# USB2Serial_MCP2200_v1_0.net
KiCad netlist of a schematic drawn in EAGLE
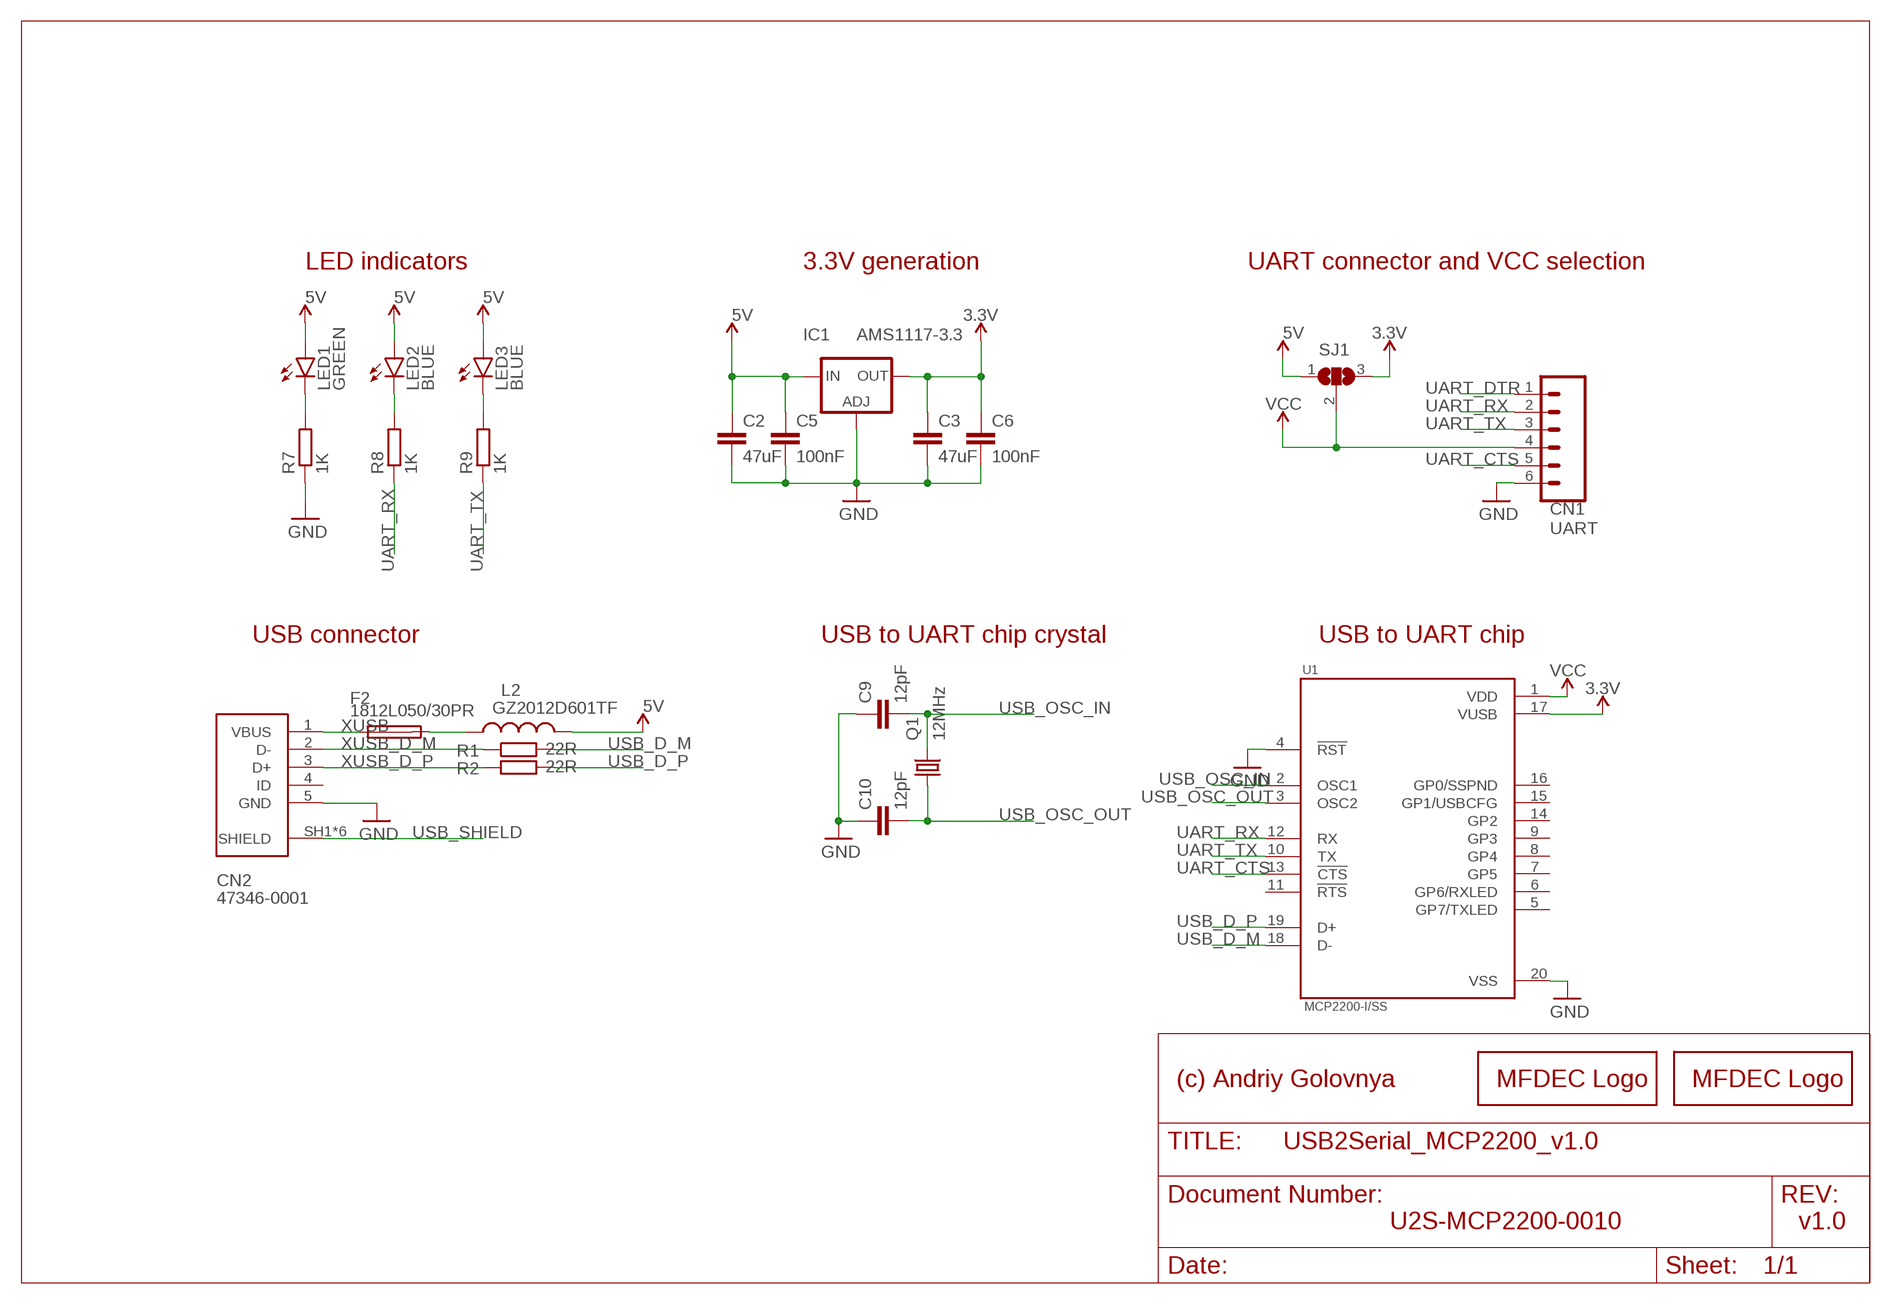
[diagram p0: schematic, sheet 1]

(export (version "E")
  (design (tool "Eeschema 10.0.6"))
  (components
    (comp (ref "C2")
      (value "47uF")
      (footprint "eagle-import:C0805")
      (libsource (lib "eagle-import") (part "C-EUC0805"))
    )
    (comp (ref "C3")
      (value "47uF")
      (footprint "eagle-import:C0805")
      (libsource (lib "eagle-import") (part "C-EUC0805"))
    )
    (comp (ref "C5")
      (value "100nF")
      (footprint "eagle-import:C0402")
      (libsource (lib "eagle-import") (part "C-EUC0402"))
    )
    (comp (ref "C6")
      (value "100nF")
      (footprint "eagle-import:C0402")
      (libsource (lib "eagle-import") (part "C-EUC0402"))
    )
    (comp (ref "C9")
      (value "12pF")
      (footprint "eagle-import:C0402")
      (libsource (lib "eagle-import") (part "C-EUC0402"))
    )
    (comp (ref "C10")
      (value "12pF")
      (footprint "eagle-import:C0402")
      (libsource (lib "eagle-import") (part "C-EUC0402"))
    )
    (comp (ref "CN1")
      (value "UART")
      (footprint "eagle-import:1X06_LOCK")
      (libsource (lib "eagle-import") (part "CONN_06LOCK"))
    )
    (comp (ref "CN2")
      (value "47346-0001")
      (footprint "eagle-import:MOLEX_47346-0001")
      (fields (field (name "MANUFACTURER") "Molex"))
      (libsource (lib "eagle-import") (part "47346-0001"))
    )
    (comp (ref "F2")
      (value "1812L050/30PR")
      (footprint "eagle-import:MF-SMDF050")
      (libsource (lib "eagle-import") (part "MF-SMDF050"))
    )
    (comp (ref "IC1")
      (value "AMS1117-3.3")
      (footprint "eagle-import:SOT223")
      (libsource (lib "eagle-import") (part "LD117A?S33TR"))
    )
    (comp (ref "L2")
      (value "GZ2012D601TF")
      (footprint "eagle-import:WE-CBA_0805(W=4)")
      (libsource (lib "eagle-import") (part "WE-CBA_0805_HC_782853102"))
    )
    (comp (ref "LED1")
      (value "GREEN")
      (footprint "eagle-import:SML0603")
      (libsource (lib "eagle-import") (part "LEDSML0603"))
    )
    (comp (ref "LED2")
      (value "BLUE")
      (footprint "eagle-import:SML0603")
      (libsource (lib "eagle-import") (part "LEDSML0603"))
    )
    (comp (ref "LED3")
      (value "BLUE")
      (footprint "eagle-import:SML0603")
      (libsource (lib "eagle-import") (part "LEDSML0603"))
    )
    (comp (ref "LOGO1")
      (value "MFDECLOGO_L_20MM")
      (footprint "eagle-import:MFDEC_L_20MM")
      (libsource (lib "eagle-import") (part "MFDECLOGO_L_20MM"))
    )
    (comp (ref "LOGO2")
      (value "MFDECLOGO_SQ_10MM")
      (footprint "eagle-import:MFDEC_SQ_10MM")
      (libsource (lib "eagle-import") (part "MFDECLOGO_SQ_10MM"))
    )
    (comp (ref "Q1")
      (value "12MHz")
      (footprint "eagle-import:3.2X2.5_KX-7")
      (libsource (lib "eagle-import") (part "KX-7"))
    )
    (comp (ref "R1")
      (value "22R")
      (footprint "eagle-import:R0402")
      (libsource (lib "eagle-import") (part "R-EU_R0402"))
    )
    (comp (ref "R2")
      (value "22R")
      (footprint "eagle-import:R0402")
      (libsource (lib "eagle-import") (part "R-EU_R0402"))
    )
    (comp (ref "R7")
      (value "1K")
      (footprint "eagle-import:R0402")
      (libsource (lib "eagle-import") (part "R-EU_R0402"))
    )
    (comp (ref "R8")
      (value "1K")
      (footprint "eagle-import:R0402")
      (libsource (lib "eagle-import") (part "R-EU_R0402"))
    )
    (comp (ref "R9")
      (value "1K")
      (footprint "eagle-import:R0402")
      (libsource (lib "eagle-import") (part "R-EU_R0402"))
    )
    (comp (ref "SJ1")
      (value "SJ2FI")
      (footprint "eagle-import:SJ_2FI")
      (libsource (lib "eagle-import") (part "SJ2FI"))
    )
    (comp (ref "U1")
      (value "MCP2200-I/SS")
      (footprint "eagle-import:SOP65P780X200-20N")
      (fields (field (name "MF") "Microchip"))
      (libsource (lib "eagle-import") (part "MCP2200-I/SS"))
    )
  )
  (nets
    (net (code "1") (name "/UART_CTS") (class "Default")
      (node (ref "CN1") (pin "5") (pinfunction "5_5") (pintype "passive"))
      (node (ref "U1") (pin "13") (pinfunction "~{CTS}_13") (pintype "input"))
    )
    (net (code "2") (name "/UART_DTR") (class "Default")
      (node (ref "CN1") (pin "1") (pinfunction "1_1") (pintype "passive"))
    )
    (net (code "3") (name "/UART_RX") (class "Default")
      (node (ref "CN1") (pin "2") (pinfunction "2_2") (pintype "passive"))
      (node (ref "R8") (pin "1") (pinfunction "1_1") (pintype "passive"))
      (node (ref "U1") (pin "12") (pinfunction "RX_12") (pintype "input"))
    )
    (net (code "4") (name "/UART_TX") (class "Default")
      (node (ref "CN1") (pin "3") (pinfunction "3_3") (pintype "passive"))
      (node (ref "R9") (pin "1") (pinfunction "1_1") (pintype "passive"))
      (node (ref "U1") (pin "10") (pinfunction "TX_10") (pintype "output"))
    )
    (net (code "5") (name "/USB_D_M") (class "Default")
      (node (ref "R1") (pin "2") (pinfunction "2_2") (pintype "passive"))
      (node (ref "U1") (pin "18") (pinfunction "D-_18") (pintype "bidirectional"))
    )
    (net (code "6") (name "/USB_D_P") (class "Default")
      (node (ref "R2") (pin "2") (pinfunction "2_2") (pintype "passive"))
      (node (ref "U1") (pin "19") (pinfunction "D+_19") (pintype "bidirectional"))
    )
    (net (code "7") (name "/USB_OSC_IN") (class "Default")
      (node (ref "C9") (pin "2") (pinfunction "2_2") (pintype "passive"))
      (node (ref "Q1") (pin "3") (pinfunction "2_3") (pintype "passive"))
      (node (ref "U1") (pin "2") (pinfunction "OSC1_2") (pintype "input"))
    )
    (net (code "8") (name "/USB_OSC_OUT") (class "Default")
      (node (ref "C10") (pin "2") (pinfunction "2_2") (pintype "passive"))
      (node (ref "Q1") (pin "1") (pinfunction "1_1") (pintype "passive"))
      (node (ref "U1") (pin "3") (pinfunction "OSC2_3") (pintype "output"))
    )
    (net (code "9") (name "/USB_SHIELD") (class "Default")
      (node (ref "CN2") (pin "SH1") (pinfunction "SHIELD_SH1") (pintype "passive"))
      (node (ref "CN2") (pin "SH2") (pinfunction "SHIELD_SH2") (pintype "passive"))
      (node (ref "CN2") (pin "SH3") (pinfunction "SHIELD_SH3") (pintype "passive"))
      (node (ref "CN2") (pin "SH4") (pinfunction "SHIELD_SH4") (pintype "passive"))
      (node (ref "CN2") (pin "SH5") (pinfunction "SHIELD_SH5") (pintype "passive"))
      (node (ref "CN2") (pin "SH6") (pinfunction "SHIELD_SH6") (pintype "passive"))
    )
    (net (code "10") (name "/XUSB") (class "Default")
      (node (ref "CN2") (pin "1") (pinfunction "VBUS_1") (pintype "power_in"))
      (node (ref "F2") (pin "1") (pinfunction "1_1") (pintype "passive"))
    )
    (net (code "11") (name "/XUSB_D_M") (class "Default")
      (node (ref "CN2") (pin "2") (pinfunction "D-_2") (pintype "bidirectional"))
      (node (ref "R1") (pin "1") (pinfunction "1_1") (pintype "passive"))
    )
    (net (code "12") (name "/XUSB_D_P") (class "Default")
      (node (ref "CN2") (pin "3") (pinfunction "D+_3") (pintype "bidirectional"))
      (node (ref "R2") (pin "1") (pinfunction "1_1") (pintype "passive"))
    )
    (net (code "13") (name "3.3V") (class "Default")
      (node (ref "C3") (pin "1") (pinfunction "1_1") (pintype "passive"))
      (node (ref "C6") (pin "1") (pinfunction "1_1") (pintype "passive"))
      (node (ref "IC1") (pin "4") (pinfunction "OUT_4") (pintype "passive"))
      (node (ref "SJ1") (pin "3") (pinfunction "3_3") (pintype "passive"))
      (node (ref "U1") (pin "17") (pinfunction "VUSB_17") (pintype "power_in"))
    )
    (net (code "14") (name "5V") (class "Default")
      (node (ref "C2") (pin "1") (pinfunction "1_1") (pintype "passive"))
      (node (ref "C5") (pin "1") (pinfunction "1_1") (pintype "passive"))
      (node (ref "IC1") (pin "3") (pinfunction "IN_3") (pintype "input"))
      (node (ref "L2") (pin "2") (pinfunction "2_2") (pintype "passive"))
      (node (ref "LED1") (pin "A") (pinfunction "A_A") (pintype "passive"))
      (node (ref "LED2") (pin "A") (pinfunction "A_A") (pintype "passive"))
      (node (ref "LED3") (pin "A") (pinfunction "A_A") (pintype "passive"))
      (node (ref "SJ1") (pin "1") (pinfunction "1_1") (pintype "passive"))
    )
    (net (code "15") (name "GND") (class "Default")
      (node (ref "C10") (pin "1") (pinfunction "1_1") (pintype "passive"))
      (node (ref "C2") (pin "2") (pinfunction "2_2") (pintype "passive"))
      (node (ref "C3") (pin "2") (pinfunction "2_2") (pintype "passive"))
      (node (ref "C5") (pin "2") (pinfunction "2_2") (pintype "passive"))
      (node (ref "C6") (pin "2") (pinfunction "2_2") (pintype "passive"))
      (node (ref "C9") (pin "1") (pinfunction "1_1") (pintype "passive"))
      (node (ref "CN1") (pin "6") (pinfunction "6_6") (pintype "passive"))
      (node (ref "CN2") (pin "5") (pinfunction "GND_5") (pintype "power_in"))
      (node (ref "IC1") (pin "1") (pinfunction "ADJ_1") (pintype "input"))
      (node (ref "R7") (pin "1") (pinfunction "1_1") (pintype "passive"))
      (node (ref "U1") (pin "20") (pinfunction "VSS_20") (pintype "power_in"))
      (node (ref "U1") (pin "4") (pinfunction "~{RST}_4") (pintype "input"))
    )
    (net (code "16") (name "Net-(F2-Pad2)") (class "Default")
      (node (ref "F2") (pin "2") (pinfunction "2_2") (pintype "passive"))
      (node (ref "L2") (pin "1") (pinfunction "1_1") (pintype "passive"))
    )
    (net (code "17") (name "Net-(LED1-PadC)") (class "Default")
      (node (ref "LED1") (pin "C") (pinfunction "C_C") (pintype "passive"))
      (node (ref "R7") (pin "2") (pinfunction "2_2") (pintype "passive"))
    )
    (net (code "18") (name "Net-(LED2-PadC)") (class "Default")
      (node (ref "LED2") (pin "C") (pinfunction "C_C") (pintype "passive"))
      (node (ref "R8") (pin "2") (pinfunction "2_2") (pintype "passive"))
    )
    (net (code "19") (name "Net-(LED3-PadC)") (class "Default")
      (node (ref "LED3") (pin "C") (pinfunction "C_C") (pintype "passive"))
      (node (ref "R9") (pin "2") (pinfunction "2_2") (pintype "passive"))
    )
    (net (code "20") (name "VCC") (class "Default")
      (node (ref "CN1") (pin "4") (pinfunction "4_4") (pintype "passive"))
      (node (ref "SJ1") (pin "2") (pinfunction "2_2") (pintype "passive"))
      (node (ref "U1") (pin "1") (pinfunction "VDD_1") (pintype "power_in"))
    )
    (net (code "21") (name "unconnected-(CN2-ID-Pad4)") (class "Default")
      (node (ref "CN2") (pin "4") (pinfunction "ID_4") (pintype "passive"))
    )
    (net (code "22") (name "unconnected-(U1-GP0{slash}SSPND-Pad16)") (class "Default")
      (node (ref "U1") (pin "16") (pinfunction "GP0/SSPND_16") (pintype "bidirectional"))
    )
    (net (code "23") (name "unconnected-(U1-GP1{slash}USBCFG-Pad15)") (class "Default")
      (node (ref "U1") (pin "15") (pinfunction "GP1/USBCFG_15") (pintype "bidirectional"))
    )
    (net (code "24") (name "unconnected-(U1-GP2-Pad14)") (class "Default")
      (node (ref "U1") (pin "14") (pinfunction "GP2_14") (pintype "bidirectional"))
    )
    (net (code "25") (name "unconnected-(U1-GP3-Pad9)") (class "Default")
      (node (ref "U1") (pin "9") (pinfunction "GP3_9") (pintype "bidirectional"))
    )
    (net (code "26") (name "unconnected-(U1-GP4-Pad8)") (class "Default")
      (node (ref "U1") (pin "8") (pinfunction "GP4_8") (pintype "bidirectional"))
    )
    (net (code "27") (name "unconnected-(U1-GP5-Pad7)") (class "Default")
      (node (ref "U1") (pin "7") (pinfunction "GP5_7") (pintype "bidirectional"))
    )
    (net (code "28") (name "unconnected-(U1-GP6{slash}RXLED-Pad6)") (class "Default")
      (node (ref "U1") (pin "6") (pinfunction "GP6/RXLED_6") (pintype "bidirectional"))
    )
    (net (code "29") (name "unconnected-(U1-GP7{slash}TXLED-Pad5)") (class "Default")
      (node (ref "U1") (pin "5") (pinfunction "GP7/TXLED_5") (pintype "bidirectional"))
    )
    (net (code "30") (name "unconnected-(U1-~{RTS}-Pad11)") (class "Default")
      (node (ref "U1") (pin "11") (pinfunction "~{RTS}_11") (pintype "output"))
    )
  )
)
